# 1_Sheet_1.net
KiCad netlist of a schematic drawn in Altium Designer
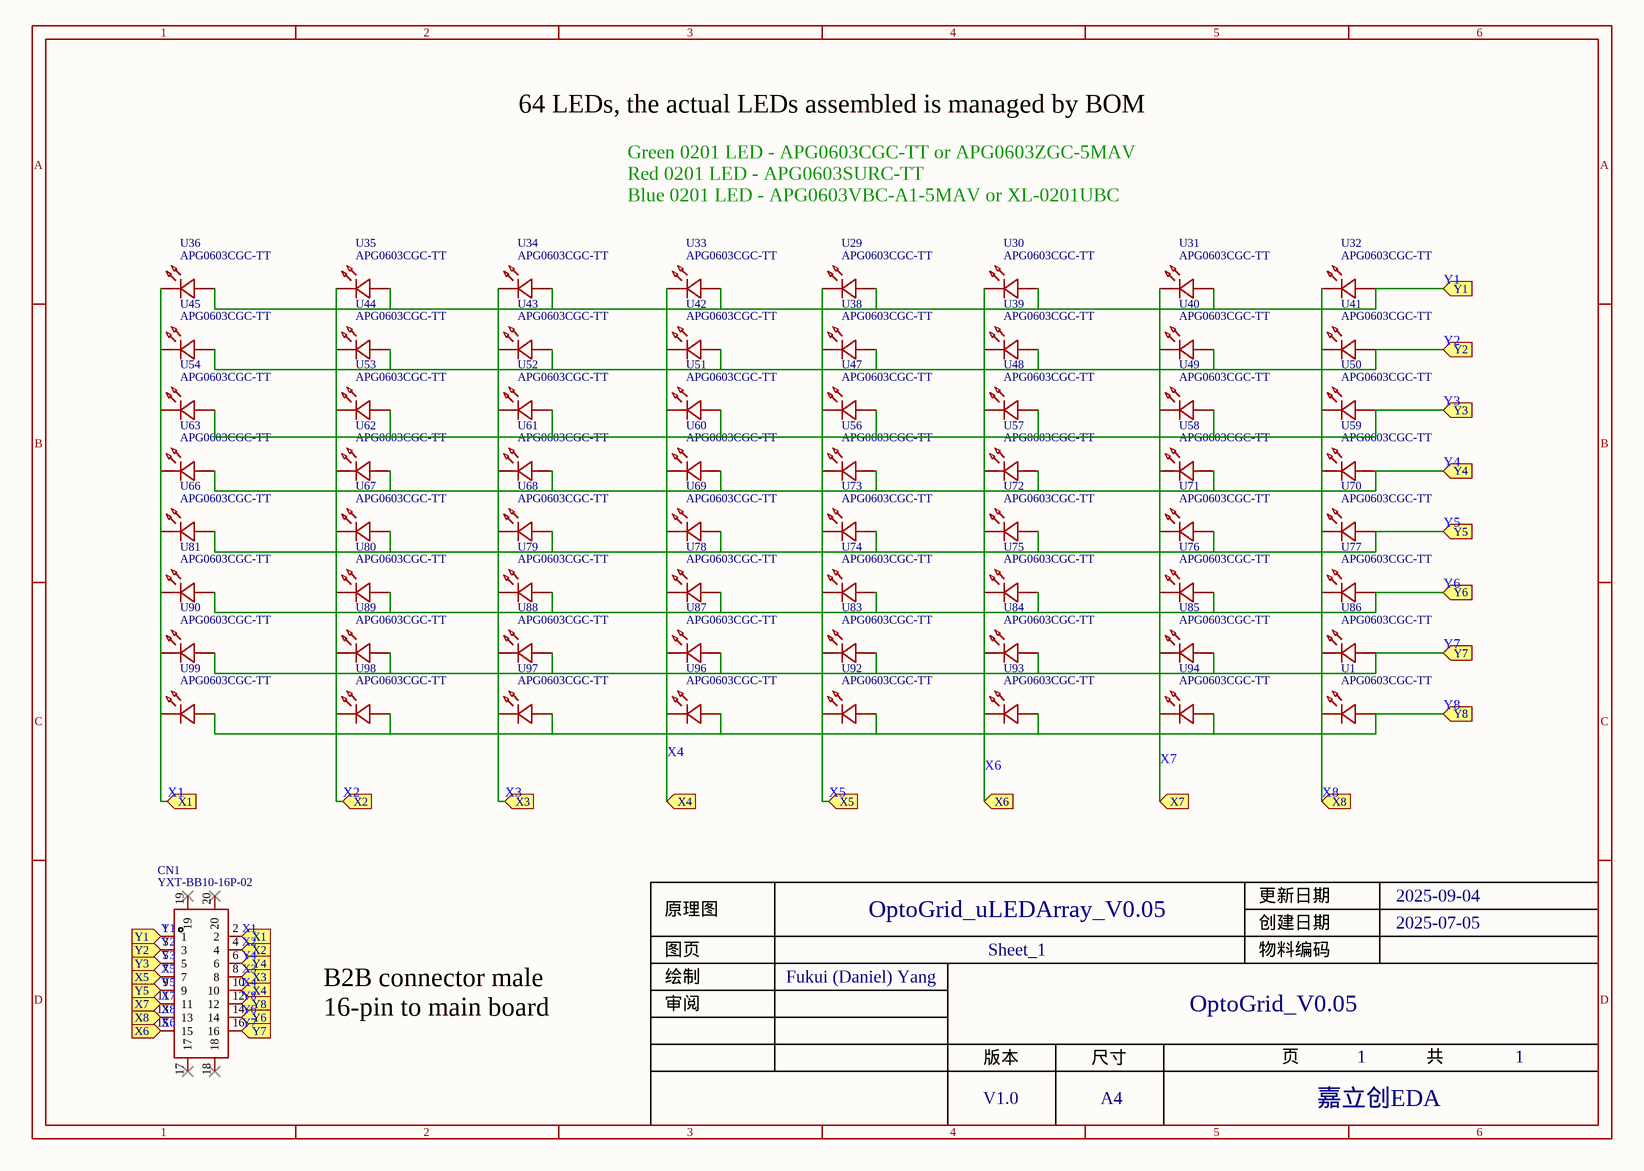
[diagram p0: 1_Sheet_1.schdoc]

(export (version "E")
  (design (tool "Eeschema 10.0.6"))
  (components
    (comp (ref "CN1")
      (value "YXT-BB10-16P-02")
      (footprint "CONN-SMD_YXT-BB10-16P-02")
      (fields (field (name "MANUFACTURER") "YXT(益鑫通）"))
      (libsource (lib "altium-import") (part "root_0_YXT-BB10-16P-02_"))
    )
    (comp (ref "U1")
      (value "APG0603CGC-TT")
      (footprint "BLUE_LED_KINGBRIGHT_0201")
      (fields (field (name "MANUFACTURER") "Kingbright"))
      (libsource (lib "altium-import") (part "root_0_APG0603VBC-A1-5MAV_"))
    )
    (comp (ref "U29")
      (value "APG0603CGC-TT")
      (footprint "BLUE_LED_KINGBRIGHT_0201")
      (fields (field (name "MANUFACTURER") "Kingbright"))
      (libsource (lib "altium-import") (part "root_0_APG0603VBC-A1-5MAV_"))
    )
    (comp (ref "U30")
      (value "APG0603CGC-TT")
      (footprint "BLUE_LED_KINGBRIGHT_0201")
      (fields (field (name "MANUFACTURER") "Kingbright"))
      (libsource (lib "altium-import") (part "root_0_APG0603VBC-A1-5MAV_"))
    )
    (comp (ref "U31")
      (value "APG0603CGC-TT")
      (footprint "BLUE_LED_KINGBRIGHT_0201")
      (fields (field (name "MANUFACTURER") "Kingbright"))
      (libsource (lib "altium-import") (part "root_0_APG0603VBC-A1-5MAV_"))
    )
    (comp (ref "U32")
      (value "APG0603CGC-TT")
      (footprint "BLUE_LED_KINGBRIGHT_0201")
      (fields (field (name "MANUFACTURER") "Kingbright"))
      (libsource (lib "altium-import") (part "root_0_APG0603VBC-A1-5MAV_"))
    )
    (comp (ref "U33")
      (value "APG0603CGC-TT")
      (footprint "BLUE_LED_KINGBRIGHT_0201")
      (fields (field (name "MANUFACTURER") "Kingbright"))
      (libsource (lib "altium-import") (part "root_0_APG0603VBC-A1-5MAV_"))
    )
    (comp (ref "U34")
      (value "APG0603CGC-TT")
      (footprint "BLUE_LED_KINGBRIGHT_0201")
      (fields (field (name "MANUFACTURER") "Kingbright"))
      (libsource (lib "altium-import") (part "root_0_APG0603VBC-A1-5MAV_"))
    )
    (comp (ref "U35")
      (value "APG0603CGC-TT")
      (footprint "BLUE_LED_KINGBRIGHT_0201")
      (fields (field (name "MANUFACTURER") "Kingbright"))
      (libsource (lib "altium-import") (part "root_0_APG0603VBC-A1-5MAV_"))
    )
    (comp (ref "U36")
      (value "APG0603CGC-TT")
      (footprint "BLUE_LED_KINGBRIGHT_0201")
      (fields (field (name "MANUFACTURER") "Kingbright"))
      (libsource (lib "altium-import") (part "root_0_APG0603VBC-A1-5MAV_"))
    )
    (comp (ref "U38")
      (value "APG0603CGC-TT")
      (footprint "BLUE_LED_KINGBRIGHT_0201")
      (fields (field (name "MANUFACTURER") "Kingbright"))
      (libsource (lib "altium-import") (part "root_0_APG0603VBC-A1-5MAV_"))
    )
    (comp (ref "U39")
      (value "APG0603CGC-TT")
      (footprint "BLUE_LED_KINGBRIGHT_0201")
      (fields (field (name "MANUFACTURER") "Kingbright"))
      (libsource (lib "altium-import") (part "root_0_APG0603VBC-A1-5MAV_"))
    )
    (comp (ref "U40")
      (value "APG0603CGC-TT")
      (footprint "BLUE_LED_KINGBRIGHT_0201")
      (fields (field (name "MANUFACTURER") "Kingbright"))
      (libsource (lib "altium-import") (part "root_0_APG0603VBC-A1-5MAV_"))
    )
    (comp (ref "U41")
      (value "APG0603CGC-TT")
      (footprint "BLUE_LED_KINGBRIGHT_0201")
      (fields (field (name "MANUFACTURER") "Kingbright"))
      (libsource (lib "altium-import") (part "root_0_APG0603VBC-A1-5MAV_"))
    )
    (comp (ref "U42")
      (value "APG0603CGC-TT")
      (footprint "BLUE_LED_KINGBRIGHT_0201")
      (fields (field (name "MANUFACTURER") "Kingbright"))
      (libsource (lib "altium-import") (part "root_0_APG0603VBC-A1-5MAV_"))
    )
    (comp (ref "U43")
      (value "APG0603CGC-TT")
      (footprint "BLUE_LED_KINGBRIGHT_0201")
      (fields (field (name "MANUFACTURER") "Kingbright"))
      (libsource (lib "altium-import") (part "root_0_APG0603VBC-A1-5MAV_"))
    )
    (comp (ref "U44")
      (value "APG0603CGC-TT")
      (footprint "BLUE_LED_KINGBRIGHT_0201")
      (fields (field (name "MANUFACTURER") "Kingbright"))
      (libsource (lib "altium-import") (part "root_0_APG0603VBC-A1-5MAV_"))
    )
    (comp (ref "U45")
      (value "APG0603CGC-TT")
      (footprint "BLUE_LED_KINGBRIGHT_0201")
      (fields (field (name "MANUFACTURER") "Kingbright"))
      (libsource (lib "altium-import") (part "root_0_APG0603VBC-A1-5MAV_"))
    )
    (comp (ref "U47")
      (value "APG0603CGC-TT")
      (footprint "BLUE_LED_KINGBRIGHT_0201")
      (fields (field (name "MANUFACTURER") "Kingbright"))
      (libsource (lib "altium-import") (part "root_0_APG0603VBC-A1-5MAV_"))
    )
    (comp (ref "U48")
      (value "APG0603CGC-TT")
      (footprint "BLUE_LED_KINGBRIGHT_0201")
      (fields (field (name "MANUFACTURER") "Kingbright"))
      (libsource (lib "altium-import") (part "root_0_APG0603VBC-A1-5MAV_"))
    )
    (comp (ref "U49")
      (value "APG0603CGC-TT")
      (footprint "BLUE_LED_KINGBRIGHT_0201")
      (fields (field (name "MANUFACTURER") "Kingbright"))
      (libsource (lib "altium-import") (part "root_0_APG0603VBC-A1-5MAV_"))
    )
    (comp (ref "U50")
      (value "APG0603CGC-TT")
      (footprint "BLUE_LED_KINGBRIGHT_0201")
      (fields (field (name "MANUFACTURER") "Kingbright"))
      (libsource (lib "altium-import") (part "root_0_APG0603VBC-A1-5MAV_"))
    )
    (comp (ref "U51")
      (value "APG0603CGC-TT")
      (footprint "BLUE_LED_KINGBRIGHT_0201")
      (fields (field (name "MANUFACTURER") "Kingbright"))
      (libsource (lib "altium-import") (part "root_0_APG0603VBC-A1-5MAV_"))
    )
    (comp (ref "U52")
      (value "APG0603CGC-TT")
      (footprint "BLUE_LED_KINGBRIGHT_0201")
      (fields (field (name "MANUFACTURER") "Kingbright"))
      (libsource (lib "altium-import") (part "root_0_APG0603VBC-A1-5MAV_"))
    )
    (comp (ref "U53")
      (value "APG0603CGC-TT")
      (footprint "BLUE_LED_KINGBRIGHT_0201")
      (fields (field (name "MANUFACTURER") "Kingbright"))
      (libsource (lib "altium-import") (part "root_0_APG0603VBC-A1-5MAV_"))
    )
    (comp (ref "U54")
      (value "APG0603CGC-TT")
      (footprint "BLUE_LED_KINGBRIGHT_0201")
      (fields (field (name "MANUFACTURER") "Kingbright"))
      (libsource (lib "altium-import") (part "root_0_APG0603VBC-A1-5MAV_"))
    )
    (comp (ref "U56")
      (value "APG0603CGC-TT")
      (footprint "BLUE_LED_KINGBRIGHT_0201")
      (fields (field (name "MANUFACTURER") "Kingbright"))
      (libsource (lib "altium-import") (part "root_0_APG0603VBC-A1-5MAV_"))
    )
    (comp (ref "U57")
      (value "APG0603CGC-TT")
      (footprint "BLUE_LED_KINGBRIGHT_0201")
      (fields (field (name "MANUFACTURER") "Kingbright"))
      (libsource (lib "altium-import") (part "root_0_APG0603VBC-A1-5MAV_"))
    )
    (comp (ref "U58")
      (value "APG0603CGC-TT")
      (footprint "BLUE_LED_KINGBRIGHT_0201")
      (fields (field (name "MANUFACTURER") "Kingbright"))
      (libsource (lib "altium-import") (part "root_0_APG0603VBC-A1-5MAV_"))
    )
    (comp (ref "U59")
      (value "APG0603CGC-TT")
      (footprint "BLUE_LED_KINGBRIGHT_0201")
      (fields (field (name "MANUFACTURER") "Kingbright"))
      (libsource (lib "altium-import") (part "root_0_APG0603VBC-A1-5MAV_"))
    )
    (comp (ref "U60")
      (value "APG0603CGC-TT")
      (footprint "BLUE_LED_KINGBRIGHT_0201")
      (fields (field (name "MANUFACTURER") "Kingbright"))
      (libsource (lib "altium-import") (part "root_0_APG0603VBC-A1-5MAV_"))
    )
    (comp (ref "U61")
      (value "APG0603CGC-TT")
      (footprint "BLUE_LED_KINGBRIGHT_0201")
      (fields (field (name "MANUFACTURER") "Kingbright"))
      (libsource (lib "altium-import") (part "root_0_APG0603VBC-A1-5MAV_"))
    )
    (comp (ref "U62")
      (value "APG0603CGC-TT")
      (footprint "BLUE_LED_KINGBRIGHT_0201")
      (fields (field (name "MANUFACTURER") "Kingbright"))
      (libsource (lib "altium-import") (part "root_0_APG0603VBC-A1-5MAV_"))
    )
    (comp (ref "U63")
      (value "APG0603CGC-TT")
      (footprint "BLUE_LED_KINGBRIGHT_0201")
      (fields (field (name "MANUFACTURER") "Kingbright"))
      (libsource (lib "altium-import") (part "root_0_APG0603VBC-A1-5MAV_"))
    )
    (comp (ref "U66")
      (value "APG0603CGC-TT")
      (footprint "BLUE_LED_KINGBRIGHT_0201")
      (fields (field (name "MANUFACTURER") "Kingbright"))
      (libsource (lib "altium-import") (part "root_0_APG0603VBC-A1-5MAV_"))
    )
    (comp (ref "U67")
      (value "APG0603CGC-TT")
      (footprint "BLUE_LED_KINGBRIGHT_0201")
      (fields (field (name "MANUFACTURER") "Kingbright"))
      (libsource (lib "altium-import") (part "root_0_APG0603VBC-A1-5MAV_"))
    )
    (comp (ref "U68")
      (value "APG0603CGC-TT")
      (footprint "BLUE_LED_KINGBRIGHT_0201")
      (fields (field (name "MANUFACTURER") "Kingbright"))
      (libsource (lib "altium-import") (part "root_0_APG0603VBC-A1-5MAV_"))
    )
    (comp (ref "U69")
      (value "APG0603CGC-TT")
      (footprint "BLUE_LED_KINGBRIGHT_0201")
      (fields (field (name "MANUFACTURER") "Kingbright"))
      (libsource (lib "altium-import") (part "root_0_APG0603VBC-A1-5MAV_"))
    )
    (comp (ref "U70")
      (value "APG0603CGC-TT")
      (footprint "BLUE_LED_KINGBRIGHT_0201")
      (fields (field (name "MANUFACTURER") "Kingbright"))
      (libsource (lib "altium-import") (part "root_0_APG0603VBC-A1-5MAV_"))
    )
    (comp (ref "U71")
      (value "APG0603CGC-TT")
      (footprint "BLUE_LED_KINGBRIGHT_0201")
      (fields (field (name "MANUFACTURER") "Kingbright"))
      (libsource (lib "altium-import") (part "root_0_APG0603VBC-A1-5MAV_"))
    )
    (comp (ref "U72")
      (value "APG0603CGC-TT")
      (footprint "BLUE_LED_KINGBRIGHT_0201")
      (fields (field (name "MANUFACTURER") "Kingbright"))
      (libsource (lib "altium-import") (part "root_0_APG0603VBC-A1-5MAV_"))
    )
    (comp (ref "U73")
      (value "APG0603CGC-TT")
      (footprint "BLUE_LED_KINGBRIGHT_0201")
      (fields (field (name "MANUFACTURER") "Kingbright"))
      (libsource (lib "altium-import") (part "root_0_APG0603VBC-A1-5MAV_"))
    )
    (comp (ref "U74")
      (value "APG0603CGC-TT")
      (footprint "BLUE_LED_KINGBRIGHT_0201")
      (fields (field (name "MANUFACTURER") "Kingbright"))
      (libsource (lib "altium-import") (part "root_0_APG0603VBC-A1-5MAV_"))
    )
    (comp (ref "U75")
      (value "APG0603CGC-TT")
      (footprint "BLUE_LED_KINGBRIGHT_0201")
      (fields (field (name "MANUFACTURER") "Kingbright"))
      (libsource (lib "altium-import") (part "root_0_APG0603VBC-A1-5MAV_"))
    )
    (comp (ref "U76")
      (value "APG0603CGC-TT")
      (footprint "BLUE_LED_KINGBRIGHT_0201")
      (fields (field (name "MANUFACTURER") "Kingbright"))
      (libsource (lib "altium-import") (part "root_0_APG0603VBC-A1-5MAV_"))
    )
    (comp (ref "U77")
      (value "APG0603CGC-TT")
      (footprint "BLUE_LED_KINGBRIGHT_0201")
      (fields (field (name "MANUFACTURER") "Kingbright"))
      (libsource (lib "altium-import") (part "root_0_APG0603VBC-A1-5MAV_"))
    )
    (comp (ref "U78")
      (value "APG0603CGC-TT")
      (footprint "BLUE_LED_KINGBRIGHT_0201")
      (fields (field (name "MANUFACTURER") "Kingbright"))
      (libsource (lib "altium-import") (part "root_0_APG0603VBC-A1-5MAV_"))
    )
    (comp (ref "U79")
      (value "APG0603CGC-TT")
      (footprint "BLUE_LED_KINGBRIGHT_0201")
      (fields (field (name "MANUFACTURER") "Kingbright"))
      (libsource (lib "altium-import") (part "root_0_APG0603VBC-A1-5MAV_"))
    )
    (comp (ref "U80")
      (value "APG0603CGC-TT")
      (footprint "BLUE_LED_KINGBRIGHT_0201")
      (fields (field (name "MANUFACTURER") "Kingbright"))
      (libsource (lib "altium-import") (part "root_0_APG0603VBC-A1-5MAV_"))
    )
    (comp (ref "U81")
      (value "APG0603CGC-TT")
      (footprint "BLUE_LED_KINGBRIGHT_0201")
      (fields (field (name "MANUFACTURER") "Kingbright"))
      (libsource (lib "altium-import") (part "root_0_APG0603VBC-A1-5MAV_"))
    )
    (comp (ref "U83")
      (value "APG0603CGC-TT")
      (footprint "BLUE_LED_KINGBRIGHT_0201")
      (fields (field (name "MANUFACTURER") "Kingbright"))
      (libsource (lib "altium-import") (part "root_0_APG0603VBC-A1-5MAV_"))
    )
    (comp (ref "U84")
      (value "APG0603CGC-TT")
      (footprint "BLUE_LED_KINGBRIGHT_0201")
      (fields (field (name "MANUFACTURER") "Kingbright"))
      (libsource (lib "altium-import") (part "root_0_APG0603VBC-A1-5MAV_"))
    )
    (comp (ref "U85")
      (value "APG0603CGC-TT")
      (footprint "BLUE_LED_KINGBRIGHT_0201")
      (fields (field (name "MANUFACTURER") "Kingbright"))
      (libsource (lib "altium-import") (part "root_0_APG0603VBC-A1-5MAV_"))
    )
    (comp (ref "U86")
      (value "APG0603CGC-TT")
      (footprint "BLUE_LED_KINGBRIGHT_0201")
      (fields (field (name "MANUFACTURER") "Kingbright"))
      (libsource (lib "altium-import") (part "root_0_APG0603VBC-A1-5MAV_"))
    )
    (comp (ref "U87")
      (value "APG0603CGC-TT")
      (footprint "BLUE_LED_KINGBRIGHT_0201")
      (fields (field (name "MANUFACTURER") "Kingbright"))
      (libsource (lib "altium-import") (part "root_0_APG0603VBC-A1-5MAV_"))
    )
    (comp (ref "U88")
      (value "APG0603CGC-TT")
      (footprint "BLUE_LED_KINGBRIGHT_0201")
      (fields (field (name "MANUFACTURER") "Kingbright"))
      (libsource (lib "altium-import") (part "root_0_APG0603VBC-A1-5MAV_"))
    )
    (comp (ref "U89")
      (value "APG0603CGC-TT")
      (footprint "BLUE_LED_KINGBRIGHT_0201")
      (fields (field (name "MANUFACTURER") "Kingbright"))
      (libsource (lib "altium-import") (part "root_0_APG0603VBC-A1-5MAV_"))
    )
    (comp (ref "U90")
      (value "APG0603CGC-TT")
      (footprint "BLUE_LED_KINGBRIGHT_0201")
      (fields (field (name "MANUFACTURER") "Kingbright"))
      (libsource (lib "altium-import") (part "root_0_APG0603VBC-A1-5MAV_"))
    )
    (comp (ref "U92")
      (value "APG0603CGC-TT")
      (footprint "BLUE_LED_KINGBRIGHT_0201")
      (fields (field (name "MANUFACTURER") "Kingbright"))
      (libsource (lib "altium-import") (part "root_0_APG0603VBC-A1-5MAV_"))
    )
    (comp (ref "U93")
      (value "APG0603CGC-TT")
      (footprint "BLUE_LED_KINGBRIGHT_0201")
      (fields (field (name "MANUFACTURER") "Kingbright"))
      (libsource (lib "altium-import") (part "root_0_APG0603VBC-A1-5MAV_"))
    )
    (comp (ref "U94")
      (value "APG0603CGC-TT")
      (footprint "BLUE_LED_KINGBRIGHT_0201")
      (fields (field (name "MANUFACTURER") "Kingbright"))
      (libsource (lib "altium-import") (part "root_0_APG0603VBC-A1-5MAV_"))
    )
    (comp (ref "U96")
      (value "APG0603CGC-TT")
      (footprint "BLUE_LED_KINGBRIGHT_0201")
      (fields (field (name "MANUFACTURER") "Kingbright"))
      (libsource (lib "altium-import") (part "root_0_APG0603VBC-A1-5MAV_"))
    )
    (comp (ref "U97")
      (value "APG0603CGC-TT")
      (footprint "BLUE_LED_KINGBRIGHT_0201")
      (fields (field (name "MANUFACTURER") "Kingbright"))
      (libsource (lib "altium-import") (part "root_0_APG0603VBC-A1-5MAV_"))
    )
    (comp (ref "U98")
      (value "APG0603CGC-TT")
      (footprint "BLUE_LED_KINGBRIGHT_0201")
      (fields (field (name "MANUFACTURER") "Kingbright"))
      (libsource (lib "altium-import") (part "root_0_APG0603VBC-A1-5MAV_"))
    )
    (comp (ref "U99")
      (value "APG0603CGC-TT")
      (footprint "BLUE_LED_KINGBRIGHT_0201")
      (fields (field (name "MANUFACTURER") "Kingbright"))
      (libsource (lib "altium-import") (part "root_0_APG0603VBC-A1-5MAV_"))
    )
  )
  (nets
    (net (code "1") (name "/X1") (class "Default")
      (node (ref "CN1") (pin "2") (pinfunction "2_2") (pintype "passive"))
      (node (ref "U36") (pin "1") (pinfunction "K_1") (pintype "passive"))
      (node (ref "U45") (pin "1") (pinfunction "K_1") (pintype "passive"))
      (node (ref "U54") (pin "1") (pinfunction "K_1") (pintype "passive"))
      (node (ref "U63") (pin "1") (pinfunction "K_1") (pintype "passive"))
      (node (ref "U66") (pin "1") (pinfunction "K_1") (pintype "passive"))
      (node (ref "U81") (pin "1") (pinfunction "K_1") (pintype "passive"))
      (node (ref "U90") (pin "1") (pinfunction "K_1") (pintype "passive"))
      (node (ref "U99") (pin "1") (pinfunction "K_1") (pintype "passive"))
    )
    (net (code "2") (name "/X2") (class "Default")
      (node (ref "CN1") (pin "4") (pinfunction "4_4") (pintype "passive"))
      (node (ref "U35") (pin "1") (pinfunction "K_1") (pintype "passive"))
      (node (ref "U44") (pin "1") (pinfunction "K_1") (pintype "passive"))
      (node (ref "U53") (pin "1") (pinfunction "K_1") (pintype "passive"))
      (node (ref "U62") (pin "1") (pinfunction "K_1") (pintype "passive"))
      (node (ref "U67") (pin "1") (pinfunction "K_1") (pintype "passive"))
      (node (ref "U80") (pin "1") (pinfunction "K_1") (pintype "passive"))
      (node (ref "U89") (pin "1") (pinfunction "K_1") (pintype "passive"))
      (node (ref "U98") (pin "1") (pinfunction "K_1") (pintype "passive"))
    )
    (net (code "3") (name "/X3") (class "Default")
      (node (ref "CN1") (pin "8") (pinfunction "8_8") (pintype "passive"))
      (node (ref "U34") (pin "1") (pinfunction "K_1") (pintype "passive"))
      (node (ref "U43") (pin "1") (pinfunction "K_1") (pintype "passive"))
      (node (ref "U52") (pin "1") (pinfunction "K_1") (pintype "passive"))
      (node (ref "U61") (pin "1") (pinfunction "K_1") (pintype "passive"))
      (node (ref "U68") (pin "1") (pinfunction "K_1") (pintype "passive"))
      (node (ref "U79") (pin "1") (pinfunction "K_1") (pintype "passive"))
      (node (ref "U88") (pin "1") (pinfunction "K_1") (pintype "passive"))
      (node (ref "U97") (pin "1") (pinfunction "K_1") (pintype "passive"))
    )
    (net (code "4") (name "/X4") (class "Default")
      (node (ref "CN1") (pin "10") (pinfunction "10_10") (pintype "passive"))
      (node (ref "U33") (pin "1") (pinfunction "K_1") (pintype "passive"))
      (node (ref "U42") (pin "1") (pinfunction "K_1") (pintype "passive"))
      (node (ref "U51") (pin "1") (pinfunction "K_1") (pintype "passive"))
      (node (ref "U60") (pin "1") (pinfunction "K_1") (pintype "passive"))
      (node (ref "U69") (pin "1") (pinfunction "K_1") (pintype "passive"))
      (node (ref "U78") (pin "1") (pinfunction "K_1") (pintype "passive"))
      (node (ref "U87") (pin "1") (pinfunction "K_1") (pintype "passive"))
      (node (ref "U96") (pin "1") (pinfunction "K_1") (pintype "passive"))
    )
    (net (code "5") (name "/X5") (class "Default")
      (node (ref "CN1") (pin "7") (pinfunction "7_7") (pintype "passive"))
      (node (ref "U29") (pin "1") (pinfunction "K_1") (pintype "passive"))
      (node (ref "U38") (pin "1") (pinfunction "K_1") (pintype "passive"))
      (node (ref "U47") (pin "1") (pinfunction "K_1") (pintype "passive"))
      (node (ref "U56") (pin "1") (pinfunction "K_1") (pintype "passive"))
      (node (ref "U73") (pin "1") (pinfunction "K_1") (pintype "passive"))
      (node (ref "U74") (pin "1") (pinfunction "K_1") (pintype "passive"))
      (node (ref "U83") (pin "1") (pinfunction "K_1") (pintype "passive"))
      (node (ref "U92") (pin "1") (pinfunction "K_1") (pintype "passive"))
    )
    (net (code "6") (name "/X6") (class "Default")
      (node (ref "CN1") (pin "15") (pinfunction "15_15") (pintype "passive"))
      (node (ref "U30") (pin "1") (pinfunction "K_1") (pintype "passive"))
      (node (ref "U39") (pin "1") (pinfunction "K_1") (pintype "passive"))
      (node (ref "U48") (pin "1") (pinfunction "K_1") (pintype "passive"))
      (node (ref "U57") (pin "1") (pinfunction "K_1") (pintype "passive"))
      (node (ref "U72") (pin "1") (pinfunction "K_1") (pintype "passive"))
      (node (ref "U75") (pin "1") (pinfunction "K_1") (pintype "passive"))
      (node (ref "U84") (pin "1") (pinfunction "K_1") (pintype "passive"))
      (node (ref "U93") (pin "1") (pinfunction "K_1") (pintype "passive"))
    )
    (net (code "7") (name "/X7") (class "Default")
      (node (ref "CN1") (pin "11") (pinfunction "11_11") (pintype "passive"))
      (node (ref "U31") (pin "1") (pinfunction "K_1") (pintype "passive"))
      (node (ref "U40") (pin "1") (pinfunction "K_1") (pintype "passive"))
      (node (ref "U49") (pin "1") (pinfunction "K_1") (pintype "passive"))
      (node (ref "U58") (pin "1") (pinfunction "K_1") (pintype "passive"))
      (node (ref "U71") (pin "1") (pinfunction "K_1") (pintype "passive"))
      (node (ref "U76") (pin "1") (pinfunction "K_1") (pintype "passive"))
      (node (ref "U85") (pin "1") (pinfunction "K_1") (pintype "passive"))
      (node (ref "U94") (pin "1") (pinfunction "K_1") (pintype "passive"))
    )
    (net (code "8") (name "/X8") (class "Default")
      (node (ref "CN1") (pin "13") (pinfunction "13_13") (pintype "passive"))
      (node (ref "U1") (pin "1") (pinfunction "K_1") (pintype "passive"))
      (node (ref "U32") (pin "1") (pinfunction "K_1") (pintype "passive"))
      (node (ref "U41") (pin "1") (pinfunction "K_1") (pintype "passive"))
      (node (ref "U50") (pin "1") (pinfunction "K_1") (pintype "passive"))
      (node (ref "U59") (pin "1") (pinfunction "K_1") (pintype "passive"))
      (node (ref "U70") (pin "1") (pinfunction "K_1") (pintype "passive"))
      (node (ref "U77") (pin "1") (pinfunction "K_1") (pintype "passive"))
      (node (ref "U86") (pin "1") (pinfunction "K_1") (pintype "passive"))
    )
    (net (code "9") (name "/Y1") (class "Default")
      (node (ref "CN1") (pin "1") (pinfunction "1_1") (pintype "passive"))
      (node (ref "U29") (pin "2") (pinfunction "A_2") (pintype "passive"))
      (node (ref "U30") (pin "2") (pinfunction "A_2") (pintype "passive"))
      (node (ref "U31") (pin "2") (pinfunction "A_2") (pintype "passive"))
      (node (ref "U32") (pin "2") (pinfunction "A_2") (pintype "passive"))
      (node (ref "U33") (pin "2") (pinfunction "A_2") (pintype "passive"))
      (node (ref "U34") (pin "2") (pinfunction "A_2") (pintype "passive"))
      (node (ref "U35") (pin "2") (pinfunction "A_2") (pintype "passive"))
      (node (ref "U36") (pin "2") (pinfunction "A_2") (pintype "passive"))
    )
    (net (code "10") (name "/Y2") (class "Default")
      (node (ref "CN1") (pin "3") (pinfunction "3_3") (pintype "passive"))
      (node (ref "U38") (pin "2") (pinfunction "A_2") (pintype "passive"))
      (node (ref "U39") (pin "2") (pinfunction "A_2") (pintype "passive"))
      (node (ref "U40") (pin "2") (pinfunction "A_2") (pintype "passive"))
      (node (ref "U41") (pin "2") (pinfunction "A_2") (pintype "passive"))
      (node (ref "U42") (pin "2") (pinfunction "A_2") (pintype "passive"))
      (node (ref "U43") (pin "2") (pinfunction "A_2") (pintype "passive"))
      (node (ref "U44") (pin "2") (pinfunction "A_2") (pintype "passive"))
      (node (ref "U45") (pin "2") (pinfunction "A_2") (pintype "passive"))
    )
    (net (code "11") (name "/Y3") (class "Default")
      (node (ref "CN1") (pin "5") (pinfunction "5_5") (pintype "passive"))
      (node (ref "U47") (pin "2") (pinfunction "A_2") (pintype "passive"))
      (node (ref "U48") (pin "2") (pinfunction "A_2") (pintype "passive"))
      (node (ref "U49") (pin "2") (pinfunction "A_2") (pintype "passive"))
      (node (ref "U50") (pin "2") (pinfunction "A_2") (pintype "passive"))
      (node (ref "U51") (pin "2") (pinfunction "A_2") (pintype "passive"))
      (node (ref "U52") (pin "2") (pinfunction "A_2") (pintype "passive"))
      (node (ref "U53") (pin "2") (pinfunction "A_2") (pintype "passive"))
      (node (ref "U54") (pin "2") (pinfunction "A_2") (pintype "passive"))
    )
    (net (code "12") (name "/Y4") (class "Default")
      (node (ref "CN1") (pin "6") (pinfunction "6_6") (pintype "passive"))
      (node (ref "U56") (pin "2") (pinfunction "A_2") (pintype "passive"))
      (node (ref "U57") (pin "2") (pinfunction "A_2") (pintype "passive"))
      (node (ref "U58") (pin "2") (pinfunction "A_2") (pintype "passive"))
      (node (ref "U59") (pin "2") (pinfunction "A_2") (pintype "passive"))
      (node (ref "U60") (pin "2") (pinfunction "A_2") (pintype "passive"))
      (node (ref "U61") (pin "2") (pinfunction "A_2") (pintype "passive"))
      (node (ref "U62") (pin "2") (pinfunction "A_2") (pintype "passive"))
      (node (ref "U63") (pin "2") (pinfunction "A_2") (pintype "passive"))
    )
    (net (code "13") (name "/Y5") (class "Default")
      (node (ref "CN1") (pin "9") (pinfunction "9_9") (pintype "passive"))
      (node (ref "U66") (pin "2") (pinfunction "A_2") (pintype "passive"))
      (node (ref "U67") (pin "2") (pinfunction "A_2") (pintype "passive"))
      (node (ref "U68") (pin "2") (pinfunction "A_2") (pintype "passive"))
      (node (ref "U69") (pin "2") (pinfunction "A_2") (pintype "passive"))
      (node (ref "U70") (pin "2") (pinfunction "A_2") (pintype "passive"))
      (node (ref "U71") (pin "2") (pinfunction "A_2") (pintype "passive"))
      (node (ref "U72") (pin "2") (pinfunction "A_2") (pintype "passive"))
      (node (ref "U73") (pin "2") (pinfunction "A_2") (pintype "passive"))
    )
    (net (code "14") (name "/Y6") (class "Default")
      (node (ref "CN1") (pin "14") (pinfunction "14_14") (pintype "passive"))
      (node (ref "U74") (pin "2") (pinfunction "A_2") (pintype "passive"))
      (node (ref "U75") (pin "2") (pinfunction "A_2") (pintype "passive"))
      (node (ref "U76") (pin "2") (pinfunction "A_2") (pintype "passive"))
      (node (ref "U77") (pin "2") (pinfunction "A_2") (pintype "passive"))
      (node (ref "U78") (pin "2") (pinfunction "A_2") (pintype "passive"))
      (node (ref "U79") (pin "2") (pinfunction "A_2") (pintype "passive"))
      (node (ref "U80") (pin "2") (pinfunction "A_2") (pintype "passive"))
      (node (ref "U81") (pin "2") (pinfunction "A_2") (pintype "passive"))
    )
    (net (code "15") (name "/Y7") (class "Default")
      (node (ref "CN1") (pin "16") (pinfunction "16_16") (pintype "passive"))
      (node (ref "U83") (pin "2") (pinfunction "A_2") (pintype "passive"))
      (node (ref "U84") (pin "2") (pinfunction "A_2") (pintype "passive"))
      (node (ref "U85") (pin "2") (pinfunction "A_2") (pintype "passive"))
      (node (ref "U86") (pin "2") (pinfunction "A_2") (pintype "passive"))
      (node (ref "U87") (pin "2") (pinfunction "A_2") (pintype "passive"))
      (node (ref "U88") (pin "2") (pinfunction "A_2") (pintype "passive"))
      (node (ref "U89") (pin "2") (pinfunction "A_2") (pintype "passive"))
      (node (ref "U90") (pin "2") (pinfunction "A_2") (pintype "passive"))
    )
    (net (code "16") (name "/Y8") (class "Default")
      (node (ref "CN1") (pin "12") (pinfunction "12_12") (pintype "passive"))
      (node (ref "U1") (pin "2") (pinfunction "A_2") (pintype "passive"))
      (node (ref "U92") (pin "2") (pinfunction "A_2") (pintype "passive"))
      (node (ref "U93") (pin "2") (pinfunction "A_2") (pintype "passive"))
      (node (ref "U94") (pin "2") (pinfunction "A_2") (pintype "passive"))
      (node (ref "U96") (pin "2") (pinfunction "A_2") (pintype "passive"))
      (node (ref "U97") (pin "2") (pinfunction "A_2") (pintype "passive"))
      (node (ref "U98") (pin "2") (pinfunction "A_2") (pintype "passive"))
      (node (ref "U99") (pin "2") (pinfunction "A_2") (pintype "passive"))
    )
    (net (code "17") (name "unconnected-(CN1-Pad17)") (class "Default")
      (node (ref "CN1") (pin "17") (pinfunction "17_17") (pintype "passive+no_connect"))
    )
    (net (code "18") (name "unconnected-(CN1-Pad18)") (class "Default")
      (node (ref "CN1") (pin "18") (pinfunction "18_18") (pintype "passive+no_connect"))
    )
    (net (code "19") (name "unconnected-(CN1-Pad19)") (class "Default")
      (node (ref "CN1") (pin "19") (pinfunction "19_19") (pintype "passive+no_connect"))
    )
    (net (code "20") (name "unconnected-(CN1-Pad20)") (class "Default")
      (node (ref "CN1") (pin "20") (pinfunction "20_20") (pintype "passive+no_connect"))
    )
  )
)
